# PFTS-IN3-PCBV1.net
KiCad netlist of a schematic drawn in Altium Designer
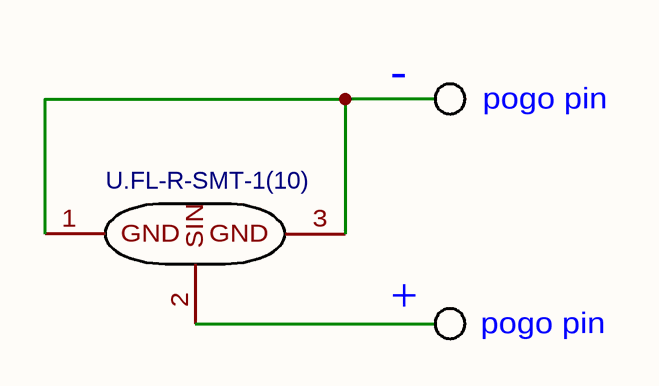
[diagram p0: PFTS-IN3-PCBV1.schdoc]

(export (version "E")
  (design (tool "Eeschema 10.0.6"))
  (components
    (comp (ref "JP1")
      (value "U.FL-R-SMT-1(10)")
      (footprint "U.FL-R-SMT-1(10)")
      (libsource (lib "altium-import") (part "root_0__"))
    )
  )
  (nets
    (net (code "1") (name "/+") (class "Default")
      (node (ref "JP1") (pin "2") (pinfunction "SIN_2") (pintype "passive"))
    )
    (net (code "2") (name "/-") (class "Default")
      (node (ref "JP1") (pin "1") (pinfunction "GND_1") (pintype "passive"))
      (node (ref "JP1") (pin "3") (pinfunction "GND_3") (pintype "passive"))
    )
  )
)
